# Kids_badge.net
KiCad netlist of a schematic drawn in EAGLE
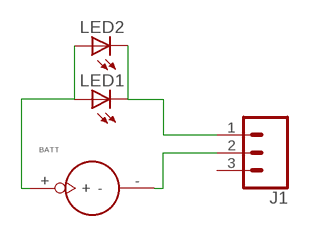
[diagram p0: schematic, sheet 1]

(export (version "E")
  (design (tool "Eeschema 10.0.6"))
  (components
    (comp (ref "BATT")
      (value "BATTERY_1236_C")
      (footprint "eagle-import:BATTERY_1236_C")
      (libsource (lib "eagle-import") (part "BATTERY_1236_C"))
    )
    (comp (ref "J1")
      (value "CONN_03LOCK")
      (footprint "eagle-import:1X03_LOCK")
      (libsource (lib "eagle-import") (part "CONN_03LOCK"))
    )
    (comp (ref "LED1")
      (value "LED5MM")
      (footprint "eagle-import:LED5MM")
      (libsource (lib "eagle-import") (part "LED5MM"))
    )
    (comp (ref "LED2")
      (value "LED5MM")
      (footprint "eagle-import:LED5MM")
      (libsource (lib "eagle-import") (part "LED5MM"))
    )
  )
  (nets
    (net (code "1") (name "Net-(BATT-Pad+)") (class "Default")
      (node (ref "BATT") (pin "+") (pinfunction "+_+") (pintype "bidirectional"))
      (node (ref "LED1") (pin "A") (pinfunction "A_A") (pintype "passive"))
      (node (ref "LED2") (pin "A") (pinfunction "A_A") (pintype "passive"))
    )
    (net (code "2") (name "Net-(BATT-Pad-)") (class "Default")
      (node (ref "BATT") (pin "-") (pinfunction "-_-") (pintype "bidirectional"))
      (node (ref "J1") (pin "2") (pinfunction "2_2") (pintype "passive"))
    )
    (net (code "3") (name "Net-(LED1-C)") (class "Default")
      (node (ref "J1") (pin "1") (pinfunction "1_1") (pintype "passive"))
      (node (ref "LED1") (pin "K") (pinfunction "C_K") (pintype "passive"))
      (node (ref "LED2") (pin "K") (pinfunction "C_K") (pintype "passive"))
    )
    (net (code "4") (name "unconnected-(J1-Pad3)") (class "Default")
      (node (ref "J1") (pin "3") (pinfunction "3_3") (pintype "passive"))
    )
  )
)
